# LM_encoder_board.net
KiCad netlist of a schematic drawn in EAGLE
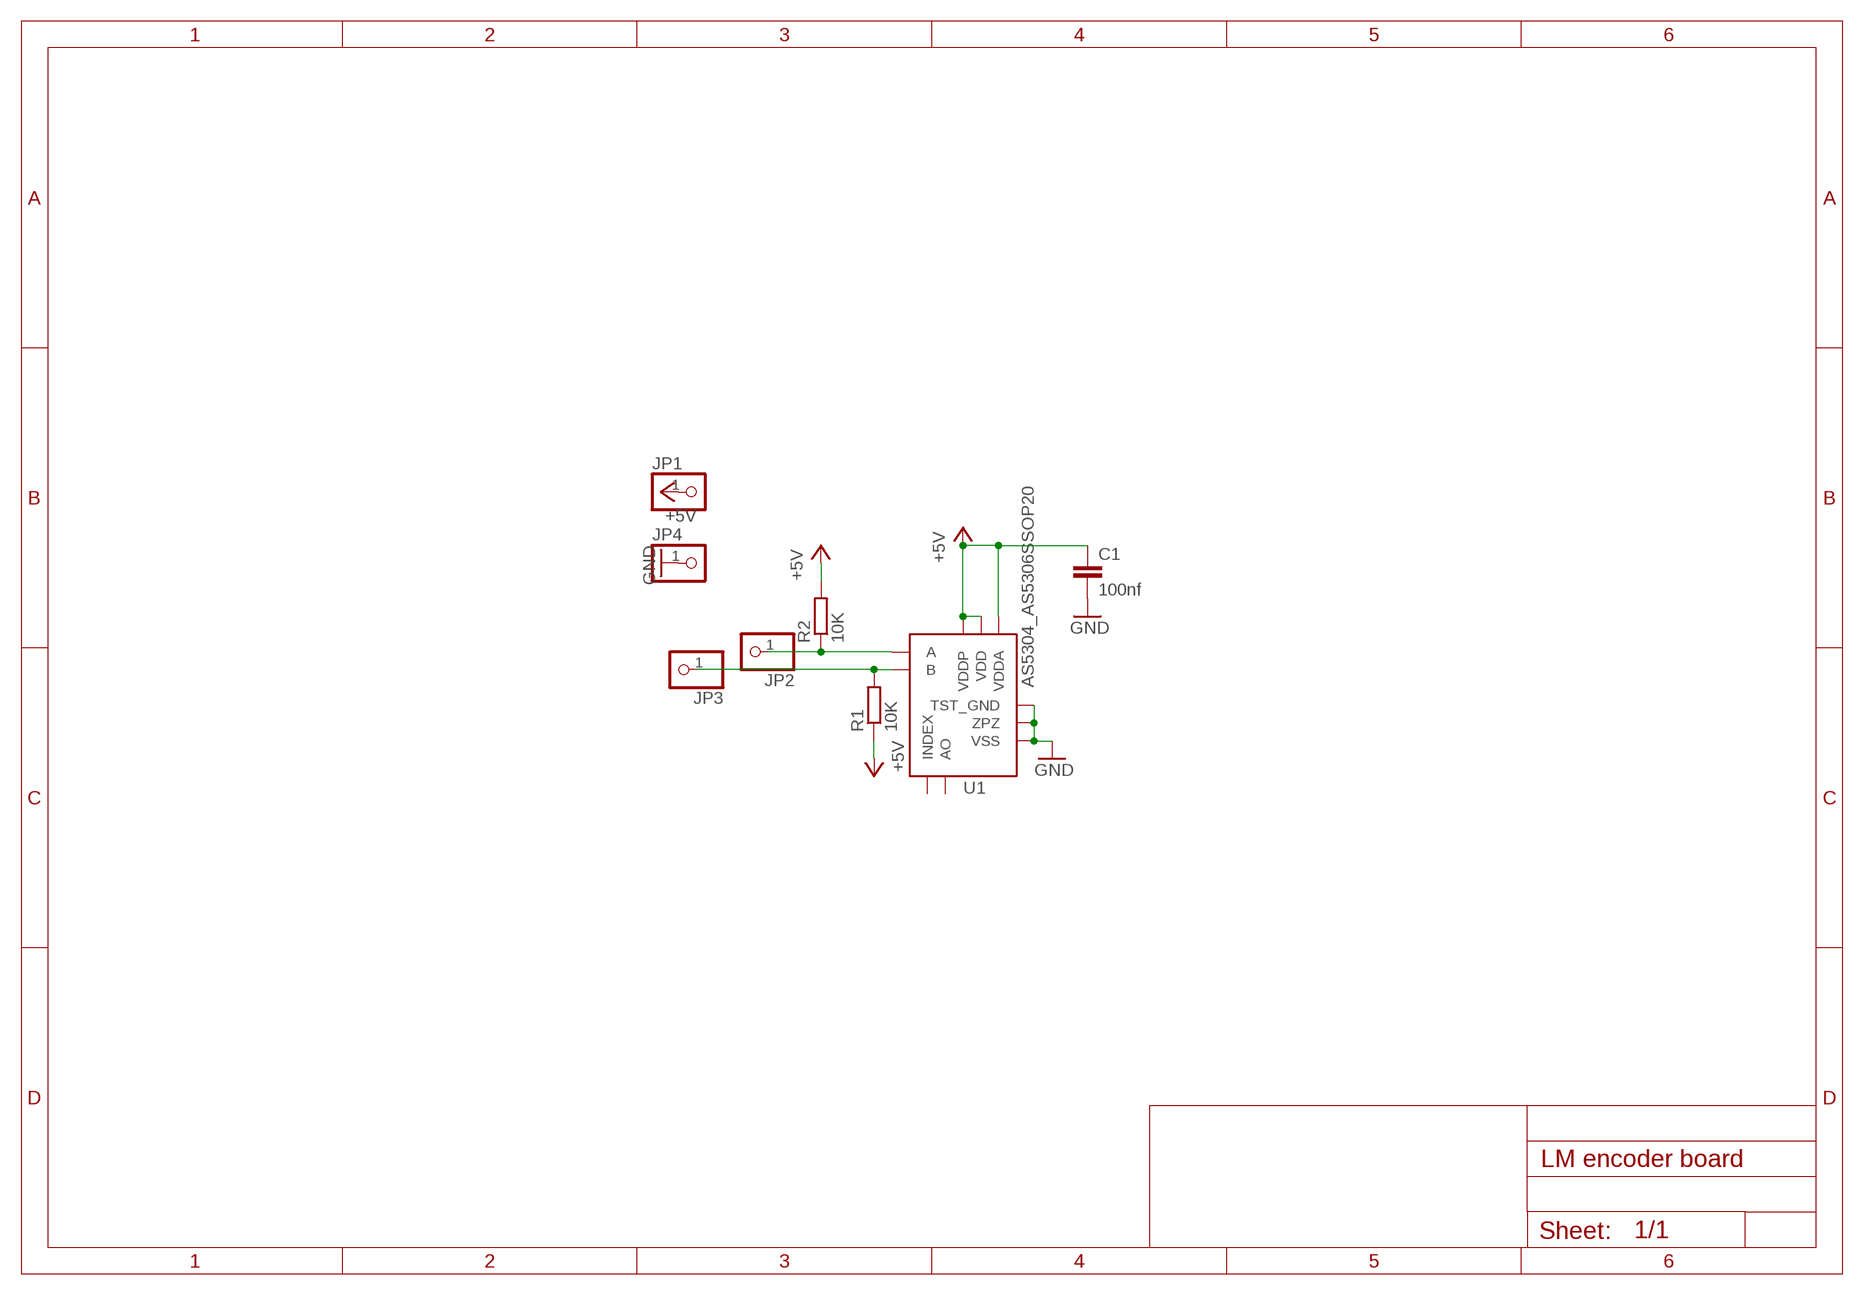
[diagram p0: schematic, sheet 1]

(export (version "E")
  (design (tool "Eeschema 10.0.6"))
  (components
    (comp (ref "C1")
      (value "100nf")
      (footprint "eagle-import:C0805")
      (libsource (lib "eagle-import") (part "C-EUC0805"))
    )
    (comp (ref "JP1")
      (value "PINHD-1X1CB")
      (footprint "eagle-import:1X01-CLEANBIG")
      (libsource (lib "eagle-import") (part "PINHD-1X1CB"))
    )
    (comp (ref "JP2")
      (value "PINHD-1X1CB")
      (footprint "eagle-import:1X01-CLEANBIG")
      (libsource (lib "eagle-import") (part "PINHD-1X1CB"))
    )
    (comp (ref "JP3")
      (value "PINHD-1X1CB")
      (footprint "eagle-import:1X01-CLEANBIG")
      (libsource (lib "eagle-import") (part "PINHD-1X1CB"))
    )
    (comp (ref "JP4")
      (value "PINHD-1X1CB")
      (footprint "eagle-import:1X01-CLEANBIG")
      (libsource (lib "eagle-import") (part "PINHD-1X1CB"))
    )
    (comp (ref "R1")
      (value "10K")
      (footprint "eagle-import:M0805")
      (libsource (lib "eagle-import") (part "R-EU_M0805"))
    )
    (comp (ref "R2")
      (value "10K")
      (footprint "eagle-import:M0805")
      (libsource (lib "eagle-import") (part "R-EU_M0805"))
    )
    (comp (ref "U1")
      (value "AS5304_AS5306SSOP20")
      (footprint "eagle-import:AS5304_5306")
      (libsource (lib "eagle-import") (part "AS5304_AS5306SSOP20"))
    )
  )
  (nets
    (net (code "1") (name "+5V") (class "Default")
      (node (ref "C1") (pin "1") (pinfunction "1_1") (pintype "passive"))
      (node (ref "JP1") (pin "1") (pinfunction "1_1") (pintype "passive"))
      (node (ref "R1") (pin "1") (pinfunction "1_1") (pintype "passive"))
      (node (ref "R2") (pin "2") (pinfunction "2_2") (pintype "passive"))
      (node (ref "U1") (pin "16") (pinfunction "VDDA_16") (pintype "power_in"))
      (node (ref "U1") (pin "3") (pinfunction "VDDP_3") (pintype "power_in"))
      (node (ref "U1") (pin "7") (pinfunction "VDD_7") (pintype "power_in"))
    )
    (net (code "2") (name "GND") (class "Default")
      (node (ref "C1") (pin "2") (pinfunction "2_2") (pintype "passive"))
      (node (ref "JP4") (pin "1") (pinfunction "1_1") (pintype "passive"))
      (node (ref "U1") (pin "1") (pinfunction "VSS_1") (pintype "power_in"))
      (node (ref "U1") (pin "15") (pinfunction "TST_GND_15") (pintype "power_in"))
      (node (ref "U1") (pin "20") (pinfunction "ZPZ_20") (pintype "power_in"))
    )
    (net (code "3") (name "Net-(U1-A)") (class "Default")
      (node (ref "JP2") (pin "1") (pinfunction "1_1") (pintype "passive"))
      (node (ref "R2") (pin "1") (pinfunction "1_1") (pintype "passive"))
      (node (ref "U1") (pin "2") (pinfunction "A_2") (pintype "output"))
    )
    (net (code "4") (name "Net-(U1-B)") (class "Default")
      (node (ref "JP3") (pin "1") (pinfunction "1_1") (pintype "passive"))
      (node (ref "R1") (pin "2") (pinfunction "2_2") (pintype "passive"))
      (node (ref "U1") (pin "4") (pinfunction "B_4") (pintype "output"))
    )
    (net (code "5") (name "unconnected-(U1-AO-Pad6)") (class "Default")
      (node (ref "U1") (pin "6") (pinfunction "AO_6") (pintype "output"))
    )
    (net (code "6") (name "unconnected-(U1-INDEX-Pad8)") (class "Default")
      (node (ref "U1") (pin "8") (pinfunction "INDEX_8") (pintype "output"))
    )
  )
)
